# temp-stellwerk-a-1.net
KiCad netlist of a schematic drawn in EAGLE
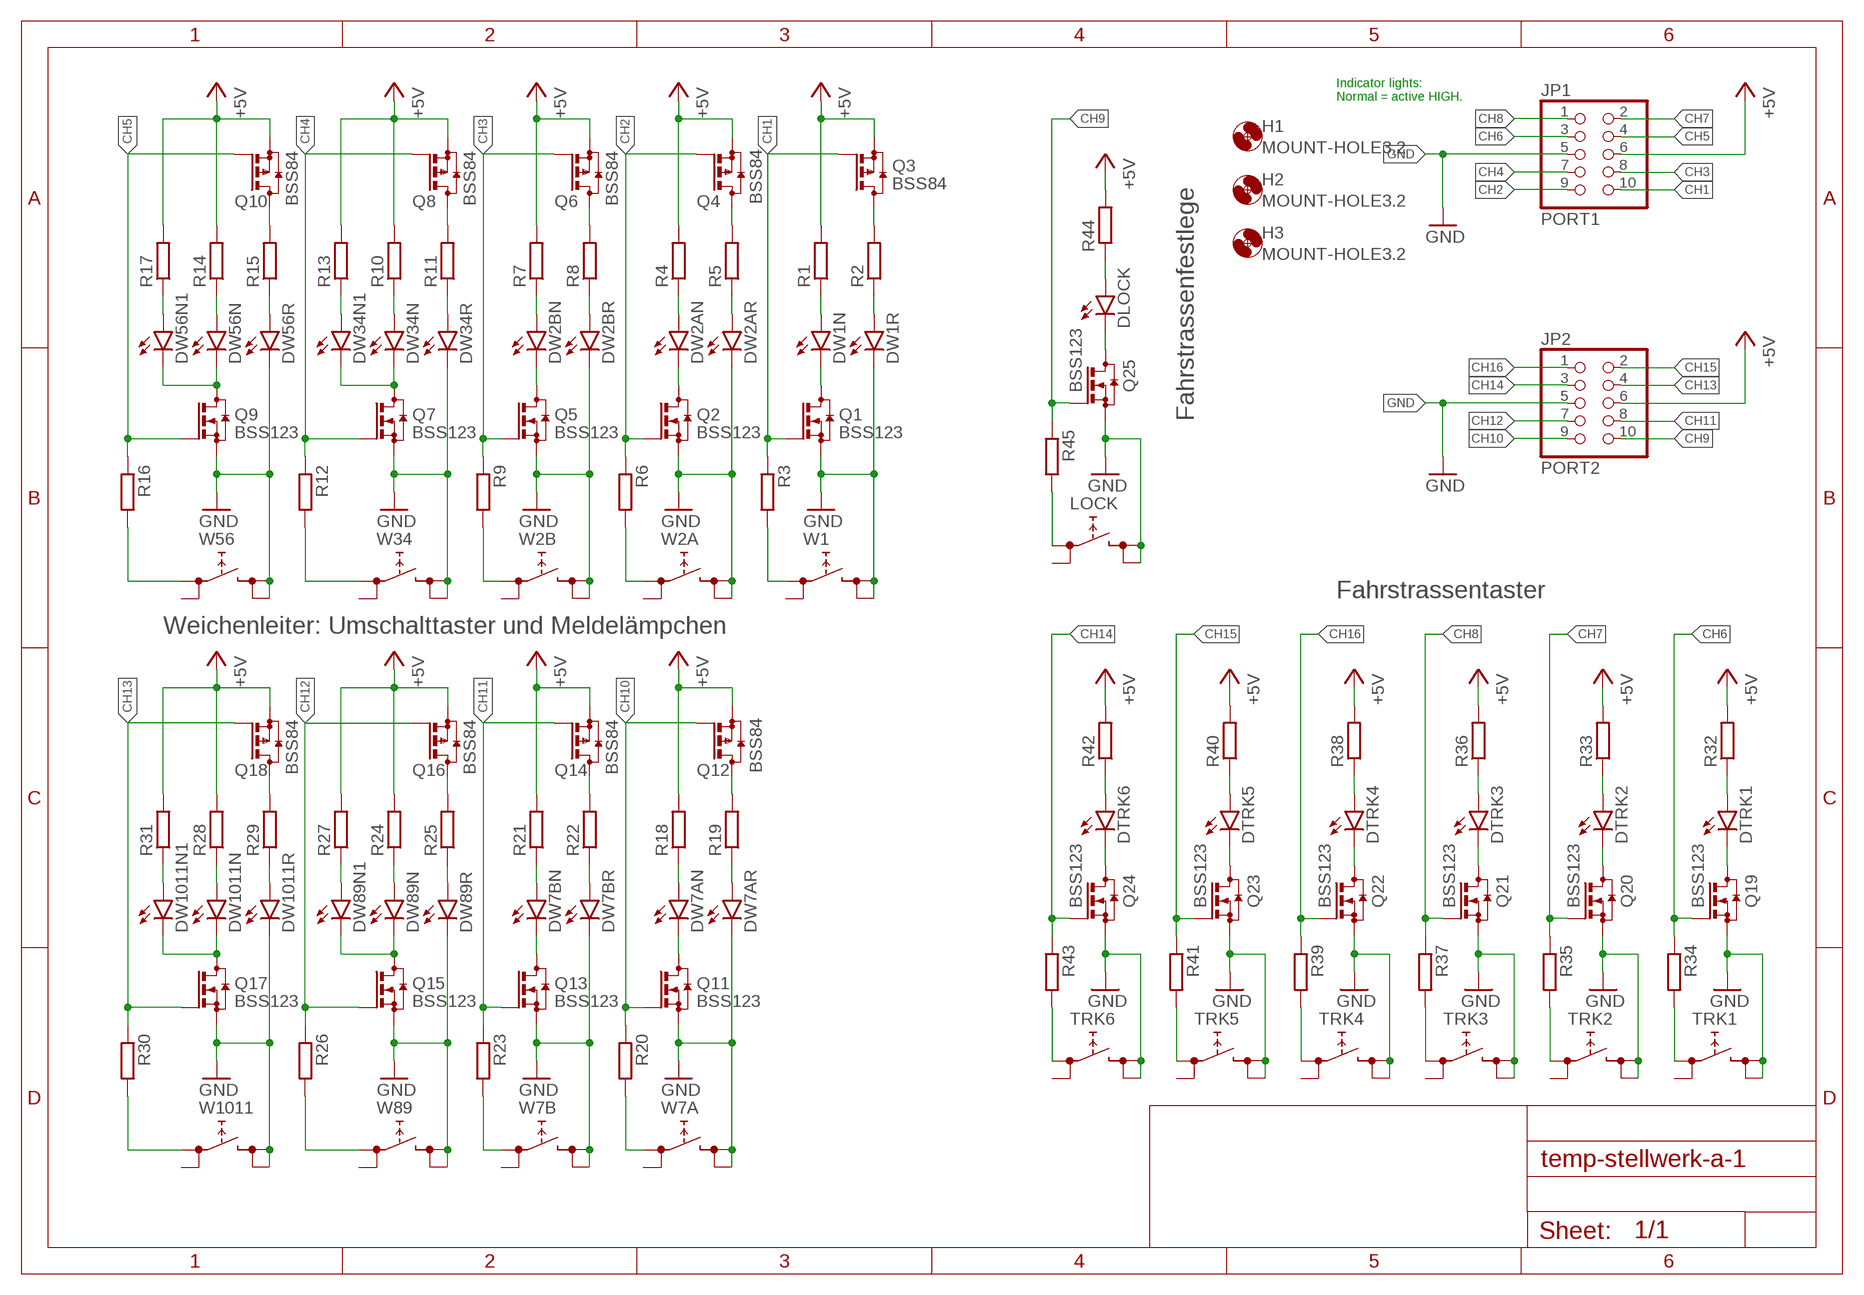
[diagram p0: schematic, sheet 1]

(export (version "E")
  (design (tool "Eeschema 10.0.6"))
  (components
    (comp (ref "DLOCK")
      (value "LEDCHIP-LED0805")
      (footprint "eagle-import:CHIP-LED0805")
      (libsource (lib "eagle-import") (part "LEDCHIP-LED0805"))
    )
    (comp (ref "DTRK1")
      (value "LEDCHIP-LED0805")
      (footprint "eagle-import:CHIP-LED0805")
      (libsource (lib "eagle-import") (part "LEDCHIP-LED0805"))
    )
    (comp (ref "DTRK2")
      (value "LEDCHIP-LED0805")
      (footprint "eagle-import:CHIP-LED0805")
      (libsource (lib "eagle-import") (part "LEDCHIP-LED0805"))
    )
    (comp (ref "DTRK3")
      (value "LEDCHIP-LED0805")
      (footprint "eagle-import:CHIP-LED0805")
      (libsource (lib "eagle-import") (part "LEDCHIP-LED0805"))
    )
    (comp (ref "DTRK4")
      (value "LEDCHIP-LED0805")
      (footprint "eagle-import:CHIP-LED0805")
      (libsource (lib "eagle-import") (part "LEDCHIP-LED0805"))
    )
    (comp (ref "DTRK5")
      (value "LEDCHIP-LED0805")
      (footprint "eagle-import:CHIP-LED0805")
      (libsource (lib "eagle-import") (part "LEDCHIP-LED0805"))
    )
    (comp (ref "DTRK6")
      (value "LEDCHIP-LED0805")
      (footprint "eagle-import:CHIP-LED0805")
      (libsource (lib "eagle-import") (part "LEDCHIP-LED0805"))
    )
    (comp (ref "DW1N")
      (value "LEDCHIP-LED0603")
      (footprint "eagle-import:CHIP-LED0603")
      (libsource (lib "eagle-import") (part "LEDCHIP-LED0603"))
    )
    (comp (ref "DW1R")
      (value "LEDCHIP-LED0603")
      (footprint "eagle-import:CHIP-LED0603")
      (libsource (lib "eagle-import") (part "LEDCHIP-LED0603"))
    )
    (comp (ref "DW2AN")
      (value "LEDCHIP-LED0603")
      (footprint "eagle-import:CHIP-LED0603")
      (libsource (lib "eagle-import") (part "LEDCHIP-LED0603"))
    )
    (comp (ref "DW2AR")
      (value "LEDCHIP-LED0603")
      (footprint "eagle-import:CHIP-LED0603")
      (libsource (lib "eagle-import") (part "LEDCHIP-LED0603"))
    )
    (comp (ref "DW2BN")
      (value "LEDCHIP-LED0805")
      (footprint "eagle-import:CHIP-LED0805")
      (libsource (lib "eagle-import") (part "LEDCHIP-LED0805"))
    )
    (comp (ref "DW2BR")
      (value "LEDCHIP-LED0805")
      (footprint "eagle-import:CHIP-LED0805")
      (libsource (lib "eagle-import") (part "LEDCHIP-LED0805"))
    )
    (comp (ref "DW7AN")
      (value "LEDCHIPLED_0603")
      (footprint "eagle-import:CHIPLED_0603")
      (libsource (lib "eagle-import") (part "LEDCHIPLED_0603"))
    )
    (comp (ref "DW7AR")
      (value "LEDCHIP-LED0603")
      (footprint "eagle-import:CHIP-LED0603")
      (libsource (lib "eagle-import") (part "LEDCHIP-LED0603"))
    )
    (comp (ref "DW7BN")
      (value "LEDCHIP-LED0805")
      (footprint "eagle-import:CHIP-LED0805")
      (libsource (lib "eagle-import") (part "LEDCHIP-LED0805"))
    )
    (comp (ref "DW7BR")
      (value "LEDCHIP-LED0805")
      (footprint "eagle-import:CHIP-LED0805")
      (libsource (lib "eagle-import") (part "LEDCHIP-LED0805"))
    )
    (comp (ref "DW34N")
      (value "LEDCHIP-LED0805")
      (footprint "eagle-import:CHIP-LED0805")
      (libsource (lib "eagle-import") (part "LEDCHIP-LED0805"))
    )
    (comp (ref "DW34N1")
      (value "LEDCHIP-LED0805")
      (footprint "eagle-import:CHIP-LED0805")
      (libsource (lib "eagle-import") (part "LEDCHIP-LED0805"))
    )
    (comp (ref "DW34R")
      (value "LEDCHIP-LED0805")
      (footprint "eagle-import:CHIP-LED0805")
      (libsource (lib "eagle-import") (part "LEDCHIP-LED0805"))
    )
    (comp (ref "DW56N")
      (value "LEDCHIP-LED0805")
      (footprint "eagle-import:CHIP-LED0805")
      (libsource (lib "eagle-import") (part "LEDCHIP-LED0805"))
    )
    (comp (ref "DW56N1")
      (value "LEDCHIP-LED0805")
      (footprint "eagle-import:CHIP-LED0805")
      (libsource (lib "eagle-import") (part "LEDCHIP-LED0805"))
    )
    (comp (ref "DW56R")
      (value "LEDCHIP-LED0805")
      (footprint "eagle-import:CHIP-LED0805")
      (libsource (lib "eagle-import") (part "LEDCHIP-LED0805"))
    )
    (comp (ref "DW89N")
      (value "LEDCHIP-LED0805")
      (footprint "eagle-import:CHIP-LED0805")
      (libsource (lib "eagle-import") (part "LEDCHIP-LED0805"))
    )
    (comp (ref "DW89N1")
      (value "LEDCHIP-LED0805")
      (footprint "eagle-import:CHIP-LED0805")
      (libsource (lib "eagle-import") (part "LEDCHIP-LED0805"))
    )
    (comp (ref "DW89R")
      (value "LEDCHIP-LED0805")
      (footprint "eagle-import:CHIP-LED0805")
      (libsource (lib "eagle-import") (part "LEDCHIP-LED0805"))
    )
    (comp (ref "DW1011N")
      (value "LEDCHIP-LED0805")
      (footprint "eagle-import:CHIP-LED0805")
      (libsource (lib "eagle-import") (part "LEDCHIP-LED0805"))
    )
    (comp (ref "DW1011N1")
      (value "LEDCHIP-LED0805")
      (footprint "eagle-import:CHIP-LED0805")
      (libsource (lib "eagle-import") (part "LEDCHIP-LED0805"))
    )
    (comp (ref "DW1011R")
      (value "LEDCHIP-LED0805")
      (footprint "eagle-import:CHIP-LED0805")
      (libsource (lib "eagle-import") (part "LEDCHIP-LED0805"))
    )
    (comp (ref "H1")
      (value "MOUNT-HOLE3.2")
      (footprint "eagle-import:3,2")
      (libsource (lib "eagle-import") (part "MOUNT-HOLE3.2"))
    )
    (comp (ref "H2")
      (value "MOUNT-HOLE3.2")
      (footprint "eagle-import:3,2")
      (libsource (lib "eagle-import") (part "MOUNT-HOLE3.2"))
    )
    (comp (ref "H3")
      (value "MOUNT-HOLE3.2")
      (footprint "eagle-import:3,2")
      (libsource (lib "eagle-import") (part "MOUNT-HOLE3.2"))
    )
    (comp (ref "JP1")
      (value "PORT1")
      (footprint "eagle-import:CON10M")
      (libsource (lib "eagle-import") (part "PINHD-2X5CN"))
    )
    (comp (ref "JP2")
      (value "PORT2")
      (footprint "eagle-import:CON10M")
      (libsource (lib "eagle-import") (part "PINHD-2X5CN"))
    )
    (comp (ref "LOCK")
      (value "LOCK")
      (footprint "eagle-import:TACTSW-6X6")
      (libsource (lib "eagle-import") (part "TACTSW-6X6S"))
    )
    (comp (ref "Q1")
      (value "BSS123")
      (footprint "eagle-import:SOT23")
      (libsource (lib "eagle-import") (part "BSS123"))
    )
    (comp (ref "Q2")
      (value "BSS123")
      (footprint "eagle-import:SOT23")
      (libsource (lib "eagle-import") (part "BSS123"))
    )
    (comp (ref "Q3")
      (value "BSS84")
      (footprint "eagle-import:SOT23")
      (libsource (lib "eagle-import") (part "BSS84"))
    )
    (comp (ref "Q4")
      (value "BSS84")
      (footprint "eagle-import:SOT23")
      (libsource (lib "eagle-import") (part "BSS84"))
    )
    (comp (ref "Q5")
      (value "BSS123")
      (footprint "eagle-import:SOT23")
      (libsource (lib "eagle-import") (part "BSS123"))
    )
    (comp (ref "Q6")
      (value "BSS84")
      (footprint "eagle-import:SOT23")
      (libsource (lib "eagle-import") (part "BSS84"))
    )
    (comp (ref "Q7")
      (value "BSS123")
      (footprint "eagle-import:SOT23")
      (libsource (lib "eagle-import") (part "BSS123"))
    )
    (comp (ref "Q8")
      (value "BSS84")
      (footprint "eagle-import:SOT23")
      (libsource (lib "eagle-import") (part "BSS84"))
    )
    (comp (ref "Q9")
      (value "BSS123")
      (footprint "eagle-import:SOT23")
      (libsource (lib "eagle-import") (part "BSS123"))
    )
    (comp (ref "Q10")
      (value "BSS84")
      (footprint "eagle-import:SOT23")
      (libsource (lib "eagle-import") (part "BSS84"))
    )
    (comp (ref "Q11")
      (value "BSS123")
      (footprint "eagle-import:SOT23")
      (libsource (lib "eagle-import") (part "BSS123"))
    )
    (comp (ref "Q12")
      (value "BSS84")
      (footprint "eagle-import:SOT23")
      (libsource (lib "eagle-import") (part "BSS84"))
    )
    (comp (ref "Q13")
      (value "BSS123")
      (footprint "eagle-import:SOT23")
      (libsource (lib "eagle-import") (part "BSS123"))
    )
    (comp (ref "Q14")
      (value "BSS84")
      (footprint "eagle-import:SOT23")
      (libsource (lib "eagle-import") (part "BSS84"))
    )
    (comp (ref "Q15")
      (value "BSS123")
      (footprint "eagle-import:SOT23")
      (libsource (lib "eagle-import") (part "BSS123"))
    )
    (comp (ref "Q16")
      (value "BSS84")
      (footprint "eagle-import:SOT23")
      (libsource (lib "eagle-import") (part "BSS84"))
    )
    (comp (ref "Q17")
      (value "BSS123")
      (footprint "eagle-import:SOT23")
      (libsource (lib "eagle-import") (part "BSS123"))
    )
    (comp (ref "Q18")
      (value "BSS84")
      (footprint "eagle-import:SOT23")
      (libsource (lib "eagle-import") (part "BSS84"))
    )
    (comp (ref "Q19")
      (value "BSS123")
      (footprint "eagle-import:SOT23")
      (libsource (lib "eagle-import") (part "BSS123"))
    )
    (comp (ref "Q20")
      (value "BSS123")
      (footprint "eagle-import:SOT23")
      (libsource (lib "eagle-import") (part "BSS123"))
    )
    (comp (ref "Q21")
      (value "BSS123")
      (footprint "eagle-import:SOT23")
      (libsource (lib "eagle-import") (part "BSS123"))
    )
    (comp (ref "Q22")
      (value "BSS123")
      (footprint "eagle-import:SOT23")
      (libsource (lib "eagle-import") (part "BSS123"))
    )
    (comp (ref "Q23")
      (value "BSS123")
      (footprint "eagle-import:SOT23")
      (libsource (lib "eagle-import") (part "BSS123"))
    )
    (comp (ref "Q24")
      (value "BSS123")
      (footprint "eagle-import:SOT23")
      (libsource (lib "eagle-import") (part "BSS123"))
    )
    (comp (ref "Q25")
      (value "BSS123")
      (footprint "eagle-import:SOT23")
      (libsource (lib "eagle-import") (part "BSS123"))
    )
    (comp (ref "R1")
      (value "R-EU_R0805")
      (footprint "eagle-import:R0805")
      (libsource (lib "eagle-import") (part "R-EU_R0805"))
    )
    (comp (ref "R2")
      (value "R-EU_R0805")
      (footprint "eagle-import:R0805")
      (libsource (lib "eagle-import") (part "R-EU_R0805"))
    )
    (comp (ref "R3")
      (value "R-EU_R0805")
      (footprint "eagle-import:R0805")
      (libsource (lib "eagle-import") (part "R-EU_R0805"))
    )
    (comp (ref "R4")
      (value "R-EU_R0805")
      (footprint "eagle-import:R0805")
      (libsource (lib "eagle-import") (part "R-EU_R0805"))
    )
    (comp (ref "R5")
      (value "R-EU_R0805")
      (footprint "eagle-import:R0805")
      (libsource (lib "eagle-import") (part "R-EU_R0805"))
    )
    (comp (ref "R6")
      (value "R-EU_R0805")
      (footprint "eagle-import:R0805")
      (libsource (lib "eagle-import") (part "R-EU_R0805"))
    )
    (comp (ref "R7")
      (value "R-EU_R0805")
      (footprint "eagle-import:R0805")
      (libsource (lib "eagle-import") (part "R-EU_R0805"))
    )
    (comp (ref "R8")
      (value "R-EU_R0805")
      (footprint "eagle-import:R0805")
      (libsource (lib "eagle-import") (part "R-EU_R0805"))
    )
    (comp (ref "R9")
      (value "R-EU_R0805")
      (footprint "eagle-import:R0805")
      (libsource (lib "eagle-import") (part "R-EU_R0805"))
    )
    (comp (ref "R10")
      (value "R-EU_R0805")
      (footprint "eagle-import:R0805")
      (libsource (lib "eagle-import") (part "R-EU_R0805"))
    )
    (comp (ref "R11")
      (value "R-EU_R0805")
      (footprint "eagle-import:R0805")
      (libsource (lib "eagle-import") (part "R-EU_R0805"))
    )
    (comp (ref "R12")
      (value "R-EU_R0805")
      (footprint "eagle-import:R0805")
      (libsource (lib "eagle-import") (part "R-EU_R0805"))
    )
    (comp (ref "R13")
      (value "R-EU_R0805")
      (footprint "eagle-import:R0805")
      (libsource (lib "eagle-import") (part "R-EU_R0805"))
    )
    (comp (ref "R14")
      (value "R-EU_R0805")
      (footprint "eagle-import:R0805")
      (libsource (lib "eagle-import") (part "R-EU_R0805"))
    )
    (comp (ref "R15")
      (value "R-EU_R0805")
      (footprint "eagle-import:R0805")
      (libsource (lib "eagle-import") (part "R-EU_R0805"))
    )
    (comp (ref "R16")
      (value "R-EU_R0805")
      (footprint "eagle-import:R0805")
      (libsource (lib "eagle-import") (part "R-EU_R0805"))
    )
    (comp (ref "R17")
      (value "R-EU_R0805")
      (footprint "eagle-import:R0805")
      (libsource (lib "eagle-import") (part "R-EU_R0805"))
    )
    (comp (ref "R18")
      (value "R-EU_R0805")
      (footprint "eagle-import:R0805")
      (libsource (lib "eagle-import") (part "R-EU_R0805"))
    )
    (comp (ref "R19")
      (value "R-EU_R0805")
      (footprint "eagle-import:R0805")
      (libsource (lib "eagle-import") (part "R-EU_R0805"))
    )
    (comp (ref "R20")
      (value "R-EU_R0805")
      (footprint "eagle-import:R0805")
      (libsource (lib "eagle-import") (part "R-EU_R0805"))
    )
    (comp (ref "R21")
      (value "R-EU_R0805")
      (footprint "eagle-import:R0805")
      (libsource (lib "eagle-import") (part "R-EU_R0805"))
    )
    (comp (ref "R22")
      (value "R-EU_R0805")
      (footprint "eagle-import:R0805")
      (libsource (lib "eagle-import") (part "R-EU_R0805"))
    )
    (comp (ref "R23")
      (value "R-EU_R0805")
      (footprint "eagle-import:R0805")
      (libsource (lib "eagle-import") (part "R-EU_R0805"))
    )
    (comp (ref "R24")
      (value "R-EU_R0805")
      (footprint "eagle-import:R0805")
      (libsource (lib "eagle-import") (part "R-EU_R0805"))
    )
    (comp (ref "R25")
      (value "R-EU_R0805")
      (footprint "eagle-import:R0805")
      (libsource (lib "eagle-import") (part "R-EU_R0805"))
    )
    (comp (ref "R26")
      (value "R-EU_R0805")
      (footprint "eagle-import:R0805")
      (libsource (lib "eagle-import") (part "R-EU_R0805"))
    )
    (comp (ref "R27")
      (value "R-EU_R0805")
      (footprint "eagle-import:R0805")
      (libsource (lib "eagle-import") (part "R-EU_R0805"))
    )
    (comp (ref "R28")
      (value "R-EU_R0805")
      (footprint "eagle-import:R0805")
      (libsource (lib "eagle-import") (part "R-EU_R0805"))
    )
    (comp (ref "R29")
      (value "R-EU_R0805")
      (footprint "eagle-import:R0805")
      (libsource (lib "eagle-import") (part "R-EU_R0805"))
    )
    (comp (ref "R30")
      (value "R-EU_R0805")
      (footprint "eagle-import:R0805")
      (libsource (lib "eagle-import") (part "R-EU_R0805"))
    )
    (comp (ref "R31")
      (value "R-EU_R0805")
      (footprint "eagle-import:R0805")
      (libsource (lib "eagle-import") (part "R-EU_R0805"))
    )
    (comp (ref "R32")
      (value "R-EU_R0805")
      (footprint "eagle-import:R0805")
      (libsource (lib "eagle-import") (part "R-EU_R0805"))
    )
    (comp (ref "R33")
      (value "R-EU_R0805")
      (footprint "eagle-import:R0805")
      (libsource (lib "eagle-import") (part "R-EU_R0805"))
    )
    (comp (ref "R34")
      (value "R-EU_R0805")
      (footprint "eagle-import:R0805")
      (libsource (lib "eagle-import") (part "R-EU_R0805"))
    )
    (comp (ref "R35")
      (value "R-EU_R0805")
      (footprint "eagle-import:R0805")
      (libsource (lib "eagle-import") (part "R-EU_R0805"))
    )
    (comp (ref "R36")
      (value "R-EU_R0805")
      (footprint "eagle-import:R0805")
      (libsource (lib "eagle-import") (part "R-EU_R0805"))
    )
    (comp (ref "R37")
      (value "R-EU_R0805")
      (footprint "eagle-import:R0805")
      (libsource (lib "eagle-import") (part "R-EU_R0805"))
    )
    (comp (ref "R38")
      (value "R-EU_R0805")
      (footprint "eagle-import:R0805")
      (libsource (lib "eagle-import") (part "R-EU_R0805"))
    )
    (comp (ref "R39")
      (value "R-EU_R0805")
      (footprint "eagle-import:R0805")
      (libsource (lib "eagle-import") (part "R-EU_R0805"))
    )
    (comp (ref "R40")
      (value "R-EU_R0805")
      (footprint "eagle-import:R0805")
      (libsource (lib "eagle-import") (part "R-EU_R0805"))
    )
    (comp (ref "R41")
      (value "R-EU_R0805")
      (footprint "eagle-import:R0805")
      (libsource (lib "eagle-import") (part "R-EU_R0805"))
    )
    (comp (ref "R42")
      (value "R-EU_R0805")
      (footprint "eagle-import:R0805")
      (libsource (lib "eagle-import") (part "R-EU_R0805"))
    )
    (comp (ref "R43")
      (value "R-EU_R0805")
      (footprint "eagle-import:R0805")
      (libsource (lib "eagle-import") (part "R-EU_R0805"))
    )
    (comp (ref "R44")
      (value "R-EU_R0805")
      (footprint "eagle-import:R0805")
      (libsource (lib "eagle-import") (part "R-EU_R0805"))
    )
    (comp (ref "R45")
      (value "R-EU_R0805")
      (footprint "eagle-import:R0805")
      (libsource (lib "eagle-import") (part "R-EU_R0805"))
    )
    (comp (ref "TRK1")
      (value "TACTSW-6X6S")
      (footprint "eagle-import:TACTSW-6X6")
      (libsource (lib "eagle-import") (part "TACTSW-6X6S"))
    )
    (comp (ref "TRK2")
      (value "TACTSW-6X6S")
      (footprint "eagle-import:TACTSW-6X6")
      (libsource (lib "eagle-import") (part "TACTSW-6X6S"))
    )
    (comp (ref "TRK3")
      (value "TACTSW-6X6S")
      (footprint "eagle-import:TACTSW-6X6")
      (libsource (lib "eagle-import") (part "TACTSW-6X6S"))
    )
    (comp (ref "TRK4")
      (value "TACTSW-6X6S")
      (footprint "eagle-import:TACTSW-6X6")
      (libsource (lib "eagle-import") (part "TACTSW-6X6S"))
    )
    (comp (ref "TRK5")
      (value "TACTSW-6X6S")
      (footprint "eagle-import:TACTSW-6X6")
      (libsource (lib "eagle-import") (part "TACTSW-6X6S"))
    )
    (comp (ref "TRK6")
      (value "TACTSW-6X6S")
      (footprint "eagle-import:TACTSW-6X6")
      (libsource (lib "eagle-import") (part "TACTSW-6X6S"))
    )
    (comp (ref "W1")
      (value "W1")
      (footprint "eagle-import:TACTSW-6X6")
      (libsource (lib "eagle-import") (part "TACTSW-6X6S"))
    )
    (comp (ref "W2A")
      (value "TACTSW-6X6S")
      (footprint "eagle-import:TACTSW-6X6")
      (libsource (lib "eagle-import") (part "TACTSW-6X6S"))
    )
    (comp (ref "W2B")
      (value "TACTSW-6X6S")
      (footprint "eagle-import:TACTSW-6X6")
      (libsource (lib "eagle-import") (part "TACTSW-6X6S"))
    )
    (comp (ref "W7A")
      (value "TACTSW-6X6S")
      (footprint "eagle-import:TACTSW-6X6")
      (libsource (lib "eagle-import") (part "TACTSW-6X6S"))
    )
    (comp (ref "W7B")
      (value "TACTSW-6X6S")
      (footprint "eagle-import:TACTSW-6X6")
      (libsource (lib "eagle-import") (part "TACTSW-6X6S"))
    )
    (comp (ref "W34")
      (value "XOVER")
      (footprint "eagle-import:TACTSW-6X6")
      (libsource (lib "eagle-import") (part "TACTSW-6X6S"))
    )
    (comp (ref "W56")
      (value "XOVER")
      (footprint "eagle-import:TACTSW-6X6")
      (libsource (lib "eagle-import") (part "TACTSW-6X6S"))
    )
    (comp (ref "W89")
      (value "XOVER")
      (footprint "eagle-import:TACTSW-6X6")
      (libsource (lib "eagle-import") (part "TACTSW-6X6S"))
    )
    (comp (ref "W1011")
      (value "XOVER")
      (footprint "eagle-import:TACTSW-6X6")
      (libsource (lib "eagle-import") (part "TACTSW-6X6S"))
    )
  )
  (nets
    (net (code "1") (name "+5V") (class "Default")
      (node (ref "JP1") (pin "6") (pinfunction "6_6") (pintype "passive"))
      (node (ref "JP2") (pin "6") (pinfunction "6_6") (pintype "passive"))
      (node (ref "Q10") (pin "2") (pinfunction "S_2") (pintype "passive"))
      (node (ref "Q12") (pin "2") (pinfunction "S_2") (pintype "passive"))
      (node (ref "Q14") (pin "2") (pinfunction "S_2") (pintype "passive"))
      (node (ref "Q16") (pin "2") (pinfunction "S_2") (pintype "passive"))
      (node (ref "Q18") (pin "2") (pinfunction "S_2") (pintype "passive"))
      (node (ref "Q3") (pin "2") (pinfunction "S_2") (pintype "passive"))
      (node (ref "Q4") (pin "2") (pinfunction "S_2") (pintype "passive"))
      (node (ref "Q6") (pin "2") (pinfunction "S_2") (pintype "passive"))
      (node (ref "Q8") (pin "2") (pinfunction "S_2") (pintype "passive"))
      (node (ref "R1") (pin "2") (pinfunction "2_2") (pintype "passive"))
      (node (ref "R10") (pin "2") (pinfunction "2_2") (pintype "passive"))
      (node (ref "R13") (pin "2") (pinfunction "2_2") (pintype "passive"))
      (node (ref "R14") (pin "2") (pinfunction "2_2") (pintype "passive"))
      (node (ref "R17") (pin "2") (pinfunction "2_2") (pintype "passive"))
      (node (ref "R18") (pin "2") (pinfunction "2_2") (pintype "passive"))
      (node (ref "R21") (pin "2") (pinfunction "2_2") (pintype "passive"))
      (node (ref "R24") (pin "2") (pinfunction "2_2") (pintype "passive"))
      (node (ref "R27") (pin "2") (pinfunction "2_2") (pintype "passive"))
      (node (ref "R28") (pin "2") (pinfunction "2_2") (pintype "passive"))
      (node (ref "R31") (pin "2") (pinfunction "2_2") (pintype "passive"))
      (node (ref "R32") (pin "2") (pinfunction "2_2") (pintype "passive"))
      (node (ref "R33") (pin "2") (pinfunction "2_2") (pintype "passive"))
      (node (ref "R36") (pin "2") (pinfunction "2_2") (pintype "passive"))
      (node (ref "R38") (pin "2") (pinfunction "2_2") (pintype "passive"))
      (node (ref "R4") (pin "2") (pinfunction "2_2") (pintype "passive"))
      (node (ref "R40") (pin "2") (pinfunction "2_2") (pintype "passive"))
      (node (ref "R42") (pin "2") (pinfunction "2_2") (pintype "passive"))
      (node (ref "R44") (pin "2") (pinfunction "2_2") (pintype "passive"))
      (node (ref "R7") (pin "2") (pinfunction "2_2") (pintype "passive"))
    )
    (net (code "2") (name "CH1") (class "Default")
      (node (ref "JP1") (pin "10") (pinfunction "10_10") (pintype "passive"))
      (node (ref "Q1") (pin "1") (pinfunction "G_1") (pintype "passive"))
      (node (ref "Q3") (pin "1") (pinfunction "G_1") (pintype "passive"))
      (node (ref "R3") (pin "1") (pinfunction "1_1") (pintype "passive"))
    )
    (net (code "3") (name "CH2") (class "Default")
      (node (ref "JP1") (pin "9") (pinfunction "9_9") (pintype "passive"))
      (node (ref "Q2") (pin "1") (pinfunction "G_1") (pintype "passive"))
      (node (ref "Q4") (pin "1") (pinfunction "G_1") (pintype "passive"))
      (node (ref "R6") (pin "1") (pinfunction "1_1") (pintype "passive"))
    )
    (net (code "4") (name "CH3") (class "Default")
      (node (ref "JP1") (pin "8") (pinfunction "8_8") (pintype "passive"))
      (node (ref "Q5") (pin "1") (pinfunction "G_1") (pintype "passive"))
      (node (ref "Q6") (pin "1") (pinfunction "G_1") (pintype "passive"))
      (node (ref "R9") (pin "1") (pinfunction "1_1") (pintype "passive"))
    )
    (net (code "5") (name "CH4") (class "Default")
      (node (ref "JP1") (pin "7") (pinfunction "7_7") (pintype "passive"))
      (node (ref "Q7") (pin "1") (pinfunction "G_1") (pintype "passive"))
      (node (ref "Q8") (pin "1") (pinfunction "G_1") (pintype "passive"))
      (node (ref "R12") (pin "1") (pinfunction "1_1") (pintype "passive"))
    )
    (net (code "6") (name "CH5") (class "Default")
      (node (ref "JP1") (pin "4") (pinfunction "4_4") (pintype "passive"))
      (node (ref "Q10") (pin "1") (pinfunction "G_1") (pintype "passive"))
      (node (ref "Q9") (pin "1") (pinfunction "G_1") (pintype "passive"))
      (node (ref "R16") (pin "1") (pinfunction "1_1") (pintype "passive"))
    )
    (net (code "7") (name "CH6") (class "Default")
      (node (ref "JP1") (pin "3") (pinfunction "3_3") (pintype "passive"))
      (node (ref "Q19") (pin "1") (pinfunction "G_1") (pintype "passive"))
      (node (ref "R34") (pin "1") (pinfunction "1_1") (pintype "passive"))
    )
    (net (code "8") (name "CH7") (class "Default")
      (node (ref "JP1") (pin "2") (pinfunction "2_2") (pintype "passive"))
      (node (ref "Q20") (pin "1") (pinfunction "G_1") (pintype "passive"))
      (node (ref "R35") (pin "1") (pinfunction "1_1") (pintype "passive"))
    )
    (net (code "9") (name "CH8") (class "Default")
      (node (ref "JP1") (pin "1") (pinfunction "1_1") (pintype "passive"))
      (node (ref "Q21") (pin "1") (pinfunction "G_1") (pintype "passive"))
      (node (ref "R37") (pin "1") (pinfunction "1_1") (pintype "passive"))
    )
    (net (code "10") (name "CH9") (class "Default")
      (node (ref "JP2") (pin "10") (pinfunction "10_10") (pintype "passive"))
      (node (ref "Q25") (pin "1") (pinfunction "G_1") (pintype "passive"))
      (node (ref "R45") (pin "1") (pinfunction "1_1") (pintype "passive"))
    )
    (net (code "11") (name "CH10") (class "Default")
      (node (ref "JP2") (pin "9") (pinfunction "9_9") (pintype "passive"))
      (node (ref "Q11") (pin "1") (pinfunction "G_1") (pintype "passive"))
      (node (ref "Q12") (pin "1") (pinfunction "G_1") (pintype "passive"))
      (node (ref "R20") (pin "1") (pinfunction "1_1") (pintype "passive"))
    )
    (net (code "12") (name "CH11") (class "Default")
      (node (ref "JP2") (pin "8") (pinfunction "8_8") (pintype "passive"))
      (node (ref "Q13") (pin "1") (pinfunction "G_1") (pintype "passive"))
      (node (ref "Q14") (pin "1") (pinfunction "G_1") (pintype "passive"))
      (node (ref "R23") (pin "1") (pinfunction "1_1") (pintype "passive"))
    )
    (net (code "13") (name "CH12") (class "Default")
      (node (ref "JP2") (pin "7") (pinfunction "7_7") (pintype "passive"))
      (node (ref "Q15") (pin "1") (pinfunction "G_1") (pintype "passive"))
      (node (ref "Q16") (pin "1") (pinfunction "G_1") (pintype "passive"))
      (node (ref "R26") (pin "1") (pinfunction "1_1") (pintype "passive"))
    )
    (net (code "14") (name "CH13") (class "Default")
      (node (ref "JP2") (pin "4") (pinfunction "4_4") (pintype "passive"))
      (node (ref "Q17") (pin "1") (pinfunction "G_1") (pintype "passive"))
      (node (ref "Q18") (pin "1") (pinfunction "G_1") (pintype "passive"))
      (node (ref "R30") (pin "1") (pinfunction "1_1") (pintype "passive"))
    )
    (net (code "15") (name "CH14") (class "Default")
      (node (ref "JP2") (pin "3") (pinfunction "3_3") (pintype "passive"))
      (node (ref "Q24") (pin "1") (pinfunction "G_1") (pintype "passive"))
      (node (ref "R43") (pin "1") (pinfunction "1_1") (pintype "passive"))
    )
    (net (code "16") (name "CH15") (class "Default")
      (node (ref "JP2") (pin "2") (pinfunction "2_2") (pintype "passive"))
      (node (ref "Q23") (pin "1") (pinfunction "G_1") (pintype "passive"))
      (node (ref "R41") (pin "1") (pinfunction "1_1") (pintype "passive"))
    )
    (net (code "17") (name "CH16") (class "Default")
      (node (ref "JP2") (pin "1") (pinfunction "1_1") (pintype "passive"))
      (node (ref "Q22") (pin "1") (pinfunction "G_1") (pintype "passive"))
      (node (ref "R39") (pin "1") (pinfunction "1_1") (pintype "passive"))
    )
    (net (code "18") (name "GND") (class "Default")
      (node (ref "DW1011R") (pin "C") (pinfunction "C_C") (pintype "passive"))
      (node (ref "DW1R") (pin "C") (pinfunction "C_C") (pintype "passive"))
      (node (ref "DW2AR") (pin "C") (pinfunction "C_C") (pintype "passive"))
      (node (ref "DW2BR") (pin "C") (pinfunction "C_C") (pintype "passive"))
      (node (ref "DW34R") (pin "C") (pinfunction "C_C") (pintype "passive"))
      (node (ref "DW56R") (pin "C") (pinfunction "C_C") (pintype "passive"))
      (node (ref "DW7AR") (pin "C") (pinfunction "C_C") (pintype "passive"))
      (node (ref "DW7BR") (pin "C") (pinfunction "C_C") (pintype "passive"))
      (node (ref "DW89R") (pin "C") (pinfunction "C_C") (pintype "passive"))
      (node (ref "JP1") (pin "5") (pinfunction "5_5") (pintype "passive"))
      (node (ref "JP2") (pin "5") (pinfunction "5_5") (pintype "passive"))
      (node (ref "LOCK") (pin "3") (pinfunction "2.1_3") (pintype "passive"))
      (node (ref "LOCK") (pin "4") (pinfunction "2.2_4") (pintype "passive"))
      (node (ref "Q1") (pin "2") (pinfunction "S_2") (pintype "passive"))
      (node (ref "Q11") (pin "2") (pinfunction "S_2") (pintype "passive"))
      (node (ref "Q13") (pin "2") (pinfunction "S_2") (pintype "passive"))
      (node (ref "Q15") (pin "2") (pinfunction "S_2") (pintype "passive"))
      (node (ref "Q17") (pin "2") (pinfunction "S_2") (pintype "passive"))
      (node (ref "Q19") (pin "2") (pinfunction "S_2") (pintype "passive"))
      (node (ref "Q2") (pin "2") (pinfunction "S_2") (pintype "passive"))
      (node (ref "Q20") (pin "2") (pinfunction "S_2") (pintype "passive"))
      (node (ref "Q21") (pin "2") (pinfunction "S_2") (pintype "passive"))
      (node (ref "Q22") (pin "2") (pinfunction "S_2") (pintype "passive"))
      (node (ref "Q23") (pin "2") (pinfunction "S_2") (pintype "passive"))
      (node (ref "Q24") (pin "2") (pinfunction "S_2") (pintype "passive"))
      (node (ref "Q25") (pin "2") (pinfunction "S_2") (pintype "passive"))
      (node (ref "Q5") (pin "2") (pinfunction "S_2") (pintype "passive"))
      (node (ref "Q7") (pin "2") (pinfunction "S_2") (pintype "passive"))
      (node (ref "Q9") (pin "2") (pinfunction "S_2") (pintype "passive"))
      (node (ref "TRK1") (pin "3") (pinfunction "2.1_3") (pintype "passive"))
      (node (ref "TRK1") (pin "4") (pinfunction "2.2_4") (pintype "passive"))
      (node (ref "TRK2") (pin "3") (pinfunction "2.1_3") (pintype "passive"))
      (node (ref "TRK2") (pin "4") (pinfunction "2.2_4") (pintype "passive"))
      (node (ref "TRK3") (pin "3") (pinfunction "2.1_3") (pintype "passive"))
      (node (ref "TRK3") (pin "4") (pinfunction "2.2_4") (pintype "passive"))
      (node (ref "TRK4") (pin "3") (pinfunction "2.1_3") (pintype "passive"))
      (node (ref "TRK4") (pin "4") (pinfunction "2.2_4") (pintype "passive"))
      (node (ref "TRK5") (pin "3") (pinfunction "2.1_3") (pintype "passive"))
      (node (ref "TRK5") (pin "4") (pinfunction "2.2_4") (pintype "passive"))
      (node (ref "TRK6") (pin "3") (pinfunction "2.1_3") (pintype "passive"))
      (node (ref "TRK6") (pin "4") (pinfunction "2.2_4") (pintype "passive"))
      (node (ref "W1") (pin "3") (pinfunction "2.1_3") (pintype "passive"))
      (node (ref "W1") (pin "4") (pinfunction "2.2_4") (pintype "passive"))
      (node (ref "W1011") (pin "3") (pinfunction "2.1_3") (pintype "passive"))
      (node (ref "W1011") (pin "4") (pinfunction "2.2_4") (pintype "passive"))
      (node (ref "W2A") (pin "3") (pinfunction "2.1_3") (pintype "passive"))
      (node (ref "W2A") (pin "4") (pinfunction "2.2_4") (pintype "passive"))
      (node (ref "W2B") (pin "3") (pinfunction "2.1_3") (pintype "passive"))
      (node (ref "W2B") (pin "4") (pinfunction "2.2_4") (pintype "passive"))
      (node (ref "W34") (pin "3") (pinfunction "2.1_3") (pintype "passive"))
      (node (ref "W34") (pin "4") (pinfunction "2.2_4") (pintype "passive"))
      (node (ref "W56") (pin "3") (pinfunction "2.1_3") (pintype "passive"))
      (node (ref "W56") (pin "4") (pinfunction "2.2_4") (pintype "passive"))
      (node (ref "W7A") (pin "3") (pinfunction "2.1_3") (pintype "passive"))
      (node (ref "W7A") (pin "4") (pinfunction "2.2_4") (pintype "passive"))
      (node (ref "W7B") (pin "3") (pinfunction "2.1_3") (pintype "passive"))
      (node (ref "W7B") (pin "4") (pinfunction "2.2_4") (pintype "passive"))
      (node (ref "W89") (pin "3") (pinfunction "2.1_3") (pintype "passive"))
      (node (ref "W89") (pin "4") (pinfunction "2.2_4") (pintype "passive"))
    )
    (net (code "19") (name "Net-(DLOCK-PadA)") (class "Default")
      (node (ref "DLOCK") (pin "A") (pinfunction "A_A") (pintype "passive"))
      (node (ref "R44") (pin "1") (pinfunction "1_1") (pintype "passive"))
    )
    (net (code "20") (name "Net-(DTRK1-PadA)") (class "Default")
      (node (ref "DTRK1") (pin "A") (pinfunction "A_A") (pintype "passive"))
      (node (ref "R32") (pin "1") (pinfunction "1_1") (pintype "passive"))
    )
    (net (code "21") (name "Net-(DTRK2-PadA)") (class "Default")
      (node (ref "DTRK2") (pin "A") (pinfunction "A_A") (pintype "passive"))
      (node (ref "R33") (pin "1") (pinfunction "1_1") (pintype "passive"))
    )
    (net (code "22") (name "Net-(DTRK3-PadA)") (class "Default")
      (node (ref "DTRK3") (pin "A") (pinfunction "A_A") (pintype "passive"))
      (node (ref "R36") (pin "1") (pinfunction "1_1") (pintype "passive"))
    )
    (net (code "23") (name "Net-(DTRK4-PadA)") (class "Default")
      (node (ref "DTRK4") (pin "A") (pinfunction "A_A") (pintype "passive"))
      (node (ref "R38") (pin "1") (pinfunction "1_1") (pintype "passive"))
    )
    (net (code "24") (name "Net-(DTRK5-PadA)") (class "Default")
      (node (ref "DTRK5") (pin "A") (pinfunction "A_A") (pintype "passive"))
      (node (ref "R40") (pin "1") (pinfunction "1_1") (pintype "passive"))
    )
    (net (code "25") (name "Net-(DTRK6-PadA)") (class "Default")
      (node (ref "DTRK6") (pin "A") (pinfunction "A_A") (pintype "passive"))
      (node (ref "R42") (pin "1") (pinfunction "1_1") (pintype "passive"))
    )
    (net (code "26") (name "Net-(DW1N-PadA)") (class "Default")
      (node (ref "DW1N") (pin "A") (pinfunction "A_A") (pintype "passive"))
      (node (ref "R1") (pin "1") (pinfunction "1_1") (pintype "passive"))
    )
    (net (code "27") (name "Net-(DW1R-PadA)") (class "Default")
      (node (ref "DW1R") (pin "A") (pinfunction "A_A") (pintype "passive"))
      (node (ref "R2") (pin "1") (pinfunction "1_1") (pintype "passive"))
    )
    (net (code "28") (name "Net-(DW2AN-PadA)") (class "Default")
      (node (ref "DW2AN") (pin "A") (pinfunction "A_A") (pintype "passive"))
      (node (ref "R4") (pin "1") (pinfunction "1_1") (pintype "passive"))
    )
    (net (code "29") (name "Net-(DW2AR-PadA)") (class "Default")
      (node (ref "DW2AR") (pin "A") (pinfunction "A_A") (pintype "passive"))
      (node (ref "R5") (pin "1") (pinfunction "1_1") (pintype "passive"))
    )
    (net (code "30") (name "Net-(DW2BN-PadA)") (class "Default")
      (node (ref "DW2BN") (pin "A") (pinfunction "A_A") (pintype "passive"))
      (node (ref "R7") (pin "1") (pinfunction "1_1") (pintype "passive"))
    )
    (net (code "31") (name "Net-(DW2BR-PadA)") (class "Default")
      (node (ref "DW2BR") (pin "A") (pinfunction "A_A") (pintype "passive"))
      (node (ref "R8") (pin "1") (pinfunction "1_1") (pintype "passive"))
    )
    (net (code "32") (name "Net-(DW7AN-PadA)") (class "Default")
      (node (ref "DW7AN") (pin "A") (pinfunction "A_A") (pintype "passive"))
      (node (ref "R18") (pin "1") (pinfunction "1_1") (pintype "passive"))
    )
    (net (code "33") (name "Net-(DW7AR-PadA)") (class "Default")
      (node (ref "DW7AR") (pin "A") (pinfunction "A_A") (pintype "passive"))
      (node (ref "R19") (pin "1") (pinfunction "1_1") (pintype "passive"))
    )
    (net (code "34") (name "Net-(DW7BN-PadA)") (class "Default")
      (node (ref "DW7BN") (pin "A") (pinfunction "A_A") (pintype "passive"))
      (node (ref "R21") (pin "1") (pinfunction "1_1") (pintype "passive"))
    )
    (net (code "35") (name "Net-(DW7BR-PadA)") (class "Default")
      (node (ref "DW7BR") (pin "A") (pinfunction "A_A") (pintype "passive"))
      (node (ref "R22") (pin "1") (pinfunction "1_1") (pintype "passive"))
    )
    (net (code "36") (name "Net-(DW34N-PadA)") (class "Default")
      (node (ref "DW34N") (pin "A") (pinfunction "A_A") (pintype "passive"))
      (node (ref "R10") (pin "1") (pinfunction "1_1") (pintype "passive"))
    )
    (net (code "37") (name "Net-(DW34N1-PadA)") (class "Default")
      (node (ref "DW34N1") (pin "A") (pinfunction "A_A") (pintype "passive"))
      (node (ref "R13") (pin "1") (pinfunction "1_1") (pintype "passive"))
    )
    (net (code "38") (name "Net-(DW34R-PadA)") (class "Default")
      (node (ref "DW34R") (pin "A") (pinfunction "A_A") (pintype "passive"))
      (node (ref "R11") (pin "1") (pinfunction "1_1") (pintype "passive"))
    )
    (net (code "39") (name "Net-(DW56N-PadA)") (class "Default")
      (node (ref "DW56N") (pin "A") (pinfunction "A_A") (pintype "passive"))
      (node (ref "R14") (pin "1") (pinfunction "1_1") (pintype "passive"))
    )
    (net (code "40") (name "Net-(DW56N1-PadA)") (class "Default")
      (node (ref "DW56N1") (pin "A") (pinfunction "A_A") (pintype "passive"))
      (node (ref "R17") (pin "1") (pinfunction "1_1") (pintype "passive"))
    )
    (net (code "41") (name "Net-(DW56R-PadA)") (class "Default")
      (node (ref "DW56R") (pin "A") (pinfunction "A_A") (pintype "passive"))
      (node (ref "R15") (pin "1") (pinfunction "1_1") (pintype "passive"))
    )
    (net (code "42") (name "Net-(DW89N-PadA)") (class "Default")
      (node (ref "DW89N") (pin "A") (pinfunction "A_A") (pintype "passive"))
      (node (ref "R24") (pin "1") (pinfunction "1_1") (pintype "passive"))
    )
    (net (code "43") (name "Net-(DW89N1-PadA)") (class "Default")
      (node (ref "DW89N1") (pin "A") (pinfunction "A_A") (pintype "passive"))
      (node (ref "R27") (pin "1") (pinfunction "1_1") (pintype "passive"))
    )
    (net (code "44") (name "Net-(DW89R-PadA)") (class "Default")
      (node (ref "DW89R") (pin "A") (pinfunction "A_A") (pintype "passive"))
      (node (ref "R25") (pin "1") (pinfunction "1_1") (pintype "passive"))
    )
    (net (code "45") (name "Net-(DW1011N-PadA)") (class "Default")
      (node (ref "DW1011N") (pin "A") (pinfunction "A_A") (pintype "passive"))
      (node (ref "R28") (pin "1") (pinfunction "1_1") (pintype "passive"))
    )
    (net (code "46") (name "Net-(DW1011N1-PadA)") (class "Default")
      (node (ref "DW1011N1") (pin "A") (pinfunction "A_A") (pintype "passive"))
      (node (ref "R31") (pin "1") (pinfunction "1_1") (pintype "passive"))
    )
    (net (code "47") (name "Net-(DW1011R-PadA)") (class "Default")
      (node (ref "DW1011R") (pin "A") (pinfunction "A_A") (pintype "passive"))
      (node (ref "R29") (pin "1") (pinfunction "1_1") (pintype "passive"))
    )
    (net (code "48") (name "Net-(LOCK-1.1)") (class "Default")
      (node (ref "LOCK") (pin "1") (pinfunction "1.1_1") (pintype "passive"))
      (node (ref "R45") (pin "2") (pinfunction "2_2") (pintype "passive"))
    )
    (net (code "49") (name "Net-(Q1-D)") (class "Default")
      (node (ref "DW1N") (pin "C") (pinfunction "C_C") (pintype "passive"))
      (node (ref "Q1") (pin "3") (pinfunction "D_3") (pintype "passive"))
    )
    (net (code "50") (name "Net-(Q2-D)") (class "Default")
      (node (ref "DW2AN") (pin "C") (pinfunction "C_C") (pintype "passive"))
      (node (ref "Q2") (pin "3") (pinfunction "D_3") (pintype "passive"))
    )
    (net (code "51") (name "Net-(Q3-D)") (class "Default")
      (node (ref "Q3") (pin "3") (pinfunction "D_3") (pintype "passive"))
      (node (ref "R2") (pin "2") (pinfunction "2_2") (pintype "passive"))
    )
    (net (code "52") (name "Net-(Q4-D)") (class "Default")
      (node (ref "Q4") (pin "3") (pinfunction "D_3") (pintype "passive"))
      (node (ref "R5") (pin "2") (pinfunction "2_2") (pintype "passive"))
    )
    (net (code "53") (name "Net-(Q5-D)") (class "Default")
      (node (ref "DW2BN") (pin "C") (pinfunction "C_C") (pintype "passive"))
      (node (ref "Q5") (pin "3") (pinfunction "D_3") (pintype "passive"))
    )
    (net (code "54") (name "Net-(Q6-D)") (class "Default")
      (node (ref "Q6") (pin "3") (pinfunction "D_3") (pintype "passive"))
      (node (ref "R8") (pin "2") (pinfunction "2_2") (pintype "passive"))
    )
    (net (code "55") (name "Net-(Q7-D)") (class "Default")
      (node (ref "DW34N") (pin "C") (pinfunction "C_C") (pintype "passive"))
      (node (ref "DW34N1") (pin "C") (pinfunction "C_C") (pintype "passive"))
      (node (ref "Q7") (pin "3") (pinfunction "D_3") (pintype "passive"))
    )
    (net (code "56") (name "Net-(Q8-D)") (class "Default")
      (node (ref "Q8") (pin "3") (pinfunction "D_3") (pintype "passive"))
      (node (ref "R11") (pin "2") (pinfunction "2_2") (pintype "passive"))
    )
    (net (code "57") (name "Net-(Q9-D)") (class "Default")
      (node (ref "DW56N") (pin "C") (pinfunction "C_C") (pintype "passive"))
      (node (ref "DW56N1") (pin "C") (pinfunction "C_C") (pintype "passive"))
      (node (ref "Q9") (pin "3") (pinfunction "D_3") (pintype "passive"))
    )
    (net (code "58") (name "Net-(Q10-D)") (class "Default")
      (node (ref "Q10") (pin "3") (pinfunction "D_3") (pintype "passive"))
      (node (ref "R15") (pin "2") (pinfunction "2_2") (pintype "passive"))
    )
    (net (code "59") (name "Net-(Q11-D)") (class "Default")
      (node (ref "DW7AN") (pin "C") (pinfunction "C_C") (pintype "passive"))
      (node (ref "Q11") (pin "3") (pinfunction "D_3") (pintype "passive"))
    )
    (net (code "60") (name "Net-(Q12-D)") (class "Default")
      (node (ref "Q12") (pin "3") (pinfunction "D_3") (pintype "passive"))
      (node (ref "R19") (pin "2") (pinfunction "2_2") (pintype "passive"))
    )
    (net (code "61") (name "Net-(Q13-D)") (class "Default")
      (node (ref "DW7BN") (pin "C") (pinfunction "C_C") (pintype "passive"))
      (node (ref "Q13") (pin "3") (pinfunction "D_3") (pintype "passive"))
    )
    (net (code "62") (name "Net-(Q14-D)") (class "Default")
      (node (ref "Q14") (pin "3") (pinfunction "D_3") (pintype "passive"))
      (node (ref "R22") (pin "2") (pinfunction "2_2") (pintype "passive"))
    )
    (net (code "63") (name "Net-(Q15-D)") (class "Default")
      (node (ref "DW89N") (pin "C") (pinfunction "C_C") (pintype "passive"))
      (node (ref "DW89N1") (pin "C") (pinfunction "C_C") (pintype "passive"))
      (node (ref "Q15") (pin "3") (pinfunction "D_3") (pintype "passive"))
    )
    (net (code "64") (name "Net-(Q16-D)") (class "Default")
      (node (ref "Q16") (pin "3") (pinfunction "D_3") (pintype "passive"))
      (node (ref "R25") (pin "2") (pinfunction "2_2") (pintype "passive"))
    )
    (net (code "65") (name "Net-(Q17-D)") (class "Default")
      (node (ref "DW1011N") (pin "C") (pinfunction "C_C") (pintype "passive"))
      (node (ref "DW1011N1") (pin "C") (pinfunction "C_C") (pintype "passive"))
      (node (ref "Q17") (pin "3") (pinfunction "D_3") (pintype "passive"))
    )
    (net (code "66") (name "Net-(Q18-D)") (class "Default")
      (node (ref "Q18") (pin "3") (pinfunction "D_3") (pintype "passive"))
      (node (ref "R29") (pin "2") (pinfunction "2_2") (pintype "passive"))
    )
    (net (code "67") (name "Net-(Q19-D)") (class "Default")
      (node (ref "DTRK1") (pin "C") (pinfunction "C_C") (pintype "passive"))
      (node (ref "Q19") (pin "3") (pinfunction "D_3") (pintype "passive"))
    )
    (net (code "68") (name "Net-(Q20-D)") (class "Default")
      (node (ref "DTRK2") (pin "C") (pinfunction "C_C") (pintype "passive"))
      (node (ref "Q20") (pin "3") (pinfunction "D_3") (pintype "passive"))
    )
    (net (code "69") (name "Net-(Q21-D)") (class "Default")
      (node (ref "DTRK3") (pin "C") (pinfunction "C_C") (pintype "passive"))
      (node (ref "Q21") (pin "3") (pinfunction "D_3") (pintype "passive"))
    )
    (net (code "70") (name "Net-(Q22-D)") (class "Default")
      (node (ref "DTRK4") (pin "C") (pinfunction "C_C") (pintype "passive"))
      (node (ref "Q22") (pin "3") (pinfunction "D_3") (pintype "passive"))
    )
    (net (code "71") (name "Net-(Q23-D)") (class "Default")
      (node (ref "DTRK5") (pin "C") (pinfunction "C_C") (pintype "passive"))
      (node (ref "Q23") (pin "3") (pinfunction "D_3") (pintype "passive"))
    )
    (net (code "72") (name "Net-(Q24-D)") (class "Default")
      (node (ref "DTRK6") (pin "C") (pinfunction "C_C") (pintype "passive"))
      (node (ref "Q24") (pin "3") (pinfunction "D_3") (pintype "passive"))
    )
    (net (code "73") (name "Net-(Q25-D)") (class "Default")
      (node (ref "DLOCK") (pin "C") (pinfunction "C_C") (pintype "passive"))
      (node (ref "Q25") (pin "3") (pinfunction "D_3") (pintype "passive"))
    )
    (net (code "74") (name "Net-(TRK1-1.1)") (class "Default")
      (node (ref "R34") (pin "2") (pinfunction "2_2") (pintype "passive"))
      (node (ref "TRK1") (pin "1") (pinfunction "1.1_1") (pintype "passive"))
    )
    (net (code "75") (name "Net-(TRK2-1.1)") (class "Default")
      (node (ref "R35") (pin "2") (pinfunction "2_2") (pintype "passive"))
      (node (ref "TRK2") (pin "1") (pinfunction "1.1_1") (pintype "passive"))
    )
    (net (code "76") (name "Net-(TRK3-1.1)") (class "Default")
      (node (ref "R37") (pin "2") (pinfunction "2_2") (pintype "passive"))
      (node (ref "TRK3") (pin "1") (pinfunction "1.1_1") (pintype "passive"))
    )
    (net (code "77") (name "Net-(TRK4-1.1)") (class "Default")
      (node (ref "R39") (pin "2") (pinfunction "2_2") (pintype "passive"))
      (node (ref "TRK4") (pin "1") (pinfunction "1.1_1") (pintype "passive"))
    )
    (net (code "78") (name "Net-(TRK5-1.1)") (class "Default")
      (node (ref "R41") (pin "2") (pinfunction "2_2") (pintype "passive"))
      (node (ref "TRK5") (pin "1") (pinfunction "1.1_1") (pintype "passive"))
    )
    (net (code "79") (name "Net-(TRK6-1.1)") (class "Default")
      (node (ref "R43") (pin "2") (pinfunction "2_2") (pintype "passive"))
      (node (ref "TRK6") (pin "1") (pinfunction "1.1_1") (pintype "passive"))
    )
    (net (code "80") (name "Net-(W1-1.1)") (class "Default")
      (node (ref "R3") (pin "2") (pinfunction "2_2") (pintype "passive"))
      (node (ref "W1") (pin "1") (pinfunction "1.1_1") (pintype "passive"))
    )
    (net (code "81") (name "Net-(W2A-1.1)") (class "Default")
      (node (ref "R6") (pin "2") (pinfunction "2_2") (pintype "passive"))
      (node (ref "W2A") (pin "1") (pinfunction "1.1_1") (pintype "passive"))
    )
    (net (code "82") (name "Net-(W2B-1.1)") (class "Default")
      (node (ref "R9") (pin "2") (pinfunction "2_2") (pintype "passive"))
      (node (ref "W2B") (pin "1") (pinfunction "1.1_1") (pintype "passive"))
    )
    (net (code "83") (name "Net-(W7A-1.1)") (class "Default")
      (node (ref "R20") (pin "2") (pinfunction "2_2") (pintype "passive"))
      (node (ref "W7A") (pin "1") (pinfunction "1.1_1") (pintype "passive"))
    )
    (net (code "84") (name "Net-(W7B-1.1)") (class "Default")
      (node (ref "R23") (pin "2") (pinfunction "2_2") (pintype "passive"))
      (node (ref "W7B") (pin "1") (pinfunction "1.1_1") (pintype "passive"))
    )
    (net (code "85") (name "Net-(W34-1.1)") (class "Default")
      (node (ref "R12") (pin "2") (pinfunction "2_2") (pintype "passive"))
      (node (ref "W34") (pin "1") (pinfunction "1.1_1") (pintype "passive"))
    )
    (net (code "86") (name "Net-(W56-1.1)") (class "Default")
      (node (ref "R16") (pin "2") (pinfunction "2_2") (pintype "passive"))
      (node (ref "W56") (pin "1") (pinfunction "1.1_1") (pintype "passive"))
    )
    (net (code "87") (name "Net-(W89-1.1)") (class "Default")
      (node (ref "R26") (pin "2") (pinfunction "2_2") (pintype "passive"))
      (node (ref "W89") (pin "1") (pinfunction "1.1_1") (pintype "passive"))
    )
    (net (code "88") (name "Net-(W1011-1.1)") (class "Default")
      (node (ref "R30") (pin "2") (pinfunction "2_2") (pintype "passive"))
      (node (ref "W1011") (pin "1") (pinfunction "1.1_1") (pintype "passive"))
    )
    (net (code "89") (name "unconnected-(LOCK-1.2-Pad2)") (class "Default")
      (node (ref "LOCK") (pin "2") (pinfunction "1.2_2") (pintype "passive"))
    )
    (net (code "90") (name "unconnected-(TRK1-1.2-Pad2)") (class "Default")
      (node (ref "TRK1") (pin "2") (pinfunction "1.2_2") (pintype "passive"))
    )
    (net (code "91") (name "unconnected-(TRK2-1.2-Pad2)") (class "Default")
      (node (ref "TRK2") (pin "2") (pinfunction "1.2_2") (pintype "passive"))
    )
    (net (code "92") (name "unconnected-(TRK3-1.2-Pad2)") (class "Default")
      (node (ref "TRK3") (pin "2") (pinfunction "1.2_2") (pintype "passive"))
    )
    (net (code "93") (name "unconnected-(TRK4-1.2-Pad2)") (class "Default")
      (node (ref "TRK4") (pin "2") (pinfunction "1.2_2") (pintype "passive"))
    )
    (net (code "94") (name "unconnected-(TRK5-1.2-Pad2)") (class "Default")
      (node (ref "TRK5") (pin "2") (pinfunction "1.2_2") (pintype "passive"))
    )
    (net (code "95") (name "unconnected-(TRK6-1.2-Pad2)") (class "Default")
      (node (ref "TRK6") (pin "2") (pinfunction "1.2_2") (pintype "passive"))
    )
    (net (code "96") (name "unconnected-(W1-1.2-Pad2)") (class "Default")
      (node (ref "W1") (pin "2") (pinfunction "1.2_2") (pintype "passive"))
    )
    (net (code "97") (name "unconnected-(W2A-1.2-Pad2)") (class "Default")
      (node (ref "W2A") (pin "2") (pinfunction "1.2_2") (pintype "passive"))
    )
    (net (code "98") (name "unconnected-(W2B-1.2-Pad2)") (class "Default")
      (node (ref "W2B") (pin "2") (pinfunction "1.2_2") (pintype "passive"))
    )
    (net (code "99") (name "unconnected-(W7A-1.2-Pad2)") (class "Default")
      (node (ref "W7A") (pin "2") (pinfunction "1.2_2") (pintype "passive"))
    )
    (net (code "100") (name "unconnected-(W7B-1.2-Pad2)") (class "Default")
      (node (ref "W7B") (pin "2") (pinfunction "1.2_2") (pintype "passive"))
    )
    (net (code "101") (name "unconnected-(W34-1.2-Pad2)") (class "Default")
      (node (ref "W34") (pin "2") (pinfunction "1.2_2") (pintype "passive"))
    )
    (net (code "102") (name "unconnected-(W56-1.2-Pad2)") (class "Default")
      (node (ref "W56") (pin "2") (pinfunction "1.2_2") (pintype "passive"))
    )
    (net (code "103") (name "unconnected-(W89-1.2-Pad2)") (class "Default")
      (node (ref "W89") (pin "2") (pinfunction "1.2_2") (pintype "passive"))
    )
    (net (code "104") (name "unconnected-(W1011-1.2-Pad2)") (class "Default")
      (node (ref "W1011") (pin "2") (pinfunction "1.2_2") (pintype "passive"))
    )
  )
)
